# main.net
KiCad netlist of a schematic drawn in Altium Designer
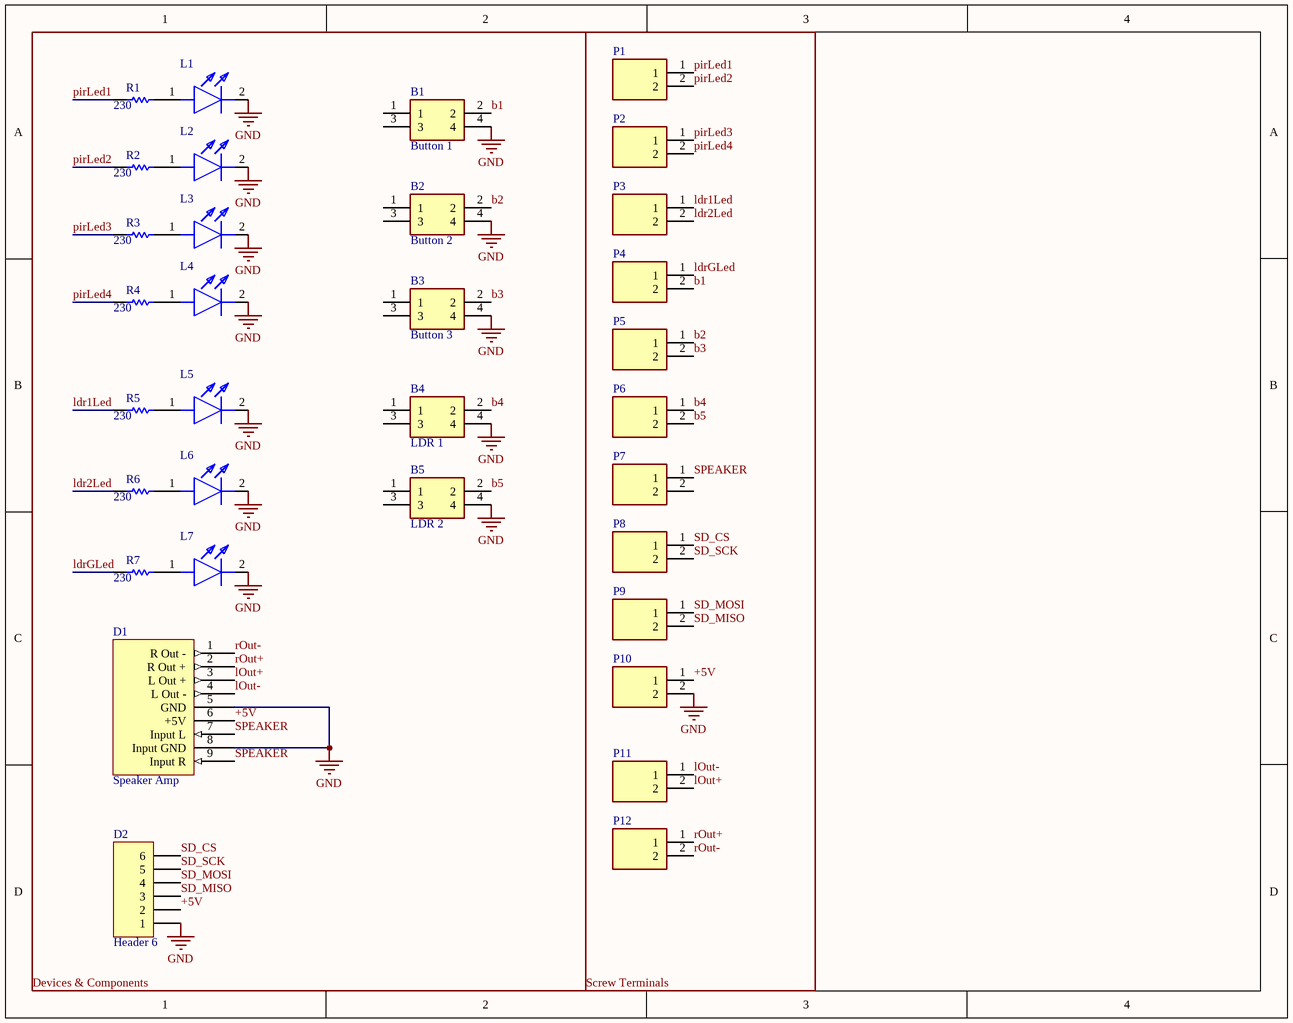
[diagram p0: main.SchDoc]

(export (version "E")
  (design (tool "Eeschema 10.0.6"))
  (components
    (comp (ref "B1")
      (value "Button 1")
      (footprint "SamacSys:FSM4JH")
      (description "Tactile Pushbutton")
      (fields
        (field (name "MANUFACTURER_PART_NUMBER") "FSM2JAH")
        (field (name "MOUSER PART NUMBER") "506-FSM2JAH")
      )
      (libsource (lib "*") (part "FSM2JAH"))
    )
    (comp (ref "B2")
      (value "Button 2")
      (footprint "SamacSys:FSM4JH")
      (description "Tactile Pushbutton")
      (fields
        (field (name "MANUFACTURER_PART_NUMBER") "FSM2JAH")
        (field (name "MOUSER PART NUMBER") "506-FSM2JAH")
      )
      (libsource (lib "*") (part "FSM2JAH"))
    )
    (comp (ref "B3")
      (value "Button 3")
      (footprint "SamacSys:FSM4JH")
      (description "Tactile Pushbutton")
      (fields
        (field (name "MANUFACTURER_PART_NUMBER") "FSM2JAH")
        (field (name "MOUSER PART NUMBER") "506-FSM2JAH")
      )
      (libsource (lib "*") (part "FSM2JAH"))
    )
    (comp (ref "B4")
      (value "LDR 1")
      (footprint "SamacSys:FSM4JH")
      (description "Tactile Pushbutton")
      (fields
        (field (name "MANUFACTURER_PART_NUMBER") "FSM2JAH")
        (field (name "MOUSER PART NUMBER") "506-FSM2JAH")
      )
      (libsource (lib "*") (part "FSM2JAH"))
    )
    (comp (ref "B5")
      (value "LDR 2")
      (footprint "SamacSys:FSM4JH")
      (description "Tactile Pushbutton")
      (fields
        (field (name "MANUFACTURER_PART_NUMBER") "FSM2JAH")
        (field (name "MOUSER PART NUMBER") "506-FSM2JAH")
      )
      (libsource (lib "*") (part "FSM2JAH"))
    )
    (comp (ref "D1")
      (value "Speaker Amp")
      (footprint "HiLetgo PAM8403 Amp Module")
      (description "https://www.amazon.com/dp/B01DKAI51M?psc=1&smid=A30QSGOJR8LMXA&ref_=chk_typ_imgToDp")
      (libsource (lib "speaker_amp") (part "HiLetgo PAM8403 Module"))
    )
    (comp (ref "D2")
      (value "Header 6")
      (footprint "HDR1X6")
      (description "Header, 6-Pin")
      (fields (field (name "PUBLISHER") "Altium Limited"))
      (libsource (lib "Miscellaneous Connectors") (part "Header 6"))
    )
    (comp (ref "L1")
      (value "~")
      (footprint "SamacSys:C5SMFRJECT0W0BB2")
      (description "LED")
      (fields
        (field (name "MANUFACTURER_PART_NUMBER") "C5SMF-RJE-CT0W0BB2")
        (field (name "MOUSER PART NUMBER") "941-C5SMFRJECT0W0BB2")
      )
      (libsource (lib "*") (part "C5SMF-RJE-CT0W0BB2"))
    )
    (comp (ref "L2")
      (value "~")
      (footprint "SamacSys:C5SMFRJECT0W0BB2")
      (description "LED")
      (fields
        (field (name "MANUFACTURER_PART_NUMBER") "C5SMF-RJE-CT0W0BB2")
        (field (name "MOUSER PART NUMBER") "941-C5SMFRJECT0W0BB2")
      )
      (libsource (lib "*") (part "C5SMF-RJE-CT0W0BB2"))
    )
    (comp (ref "L3")
      (value "~")
      (footprint "SamacSys:C5SMFRJECT0W0BB2")
      (description "LED")
      (fields
        (field (name "MANUFACTURER_PART_NUMBER") "C5SMF-RJE-CT0W0BB2")
        (field (name "MOUSER PART NUMBER") "941-C5SMFRJECT0W0BB2")
      )
      (libsource (lib "*") (part "C5SMF-RJE-CT0W0BB2"))
    )
    (comp (ref "L4")
      (value "~")
      (footprint "SamacSys:C5SMFRJECT0W0BB2")
      (description "LED")
      (fields
        (field (name "MANUFACTURER_PART_NUMBER") "C5SMF-RJE-CT0W0BB2")
        (field (name "MOUSER PART NUMBER") "941-C5SMFRJECT0W0BB2")
      )
      (libsource (lib "*") (part "C5SMF-RJE-CT0W0BB2"))
    )
    (comp (ref "L5")
      (value "~")
      (footprint "SamacSys:C5SMFRJECT0W0BB2")
      (description "LED")
      (fields
        (field (name "MANUFACTURER_PART_NUMBER") "C5SMF-RJE-CT0W0BB2")
        (field (name "MOUSER PART NUMBER") "941-C5SMFRJECT0W0BB2")
      )
      (libsource (lib "*") (part "C5SMF-RJE-CT0W0BB2"))
    )
    (comp (ref "L6")
      (value "~")
      (footprint "SamacSys:C5SMFRJECT0W0BB2")
      (description "LED")
      (fields
        (field (name "MANUFACTURER_PART_NUMBER") "C5SMF-RJE-CT0W0BB2")
        (field (name "MOUSER PART NUMBER") "941-C5SMFRJECT0W0BB2")
      )
      (libsource (lib "*") (part "C5SMF-RJE-CT0W0BB2"))
    )
    (comp (ref "L7")
      (value "~")
      (footprint "SamacSys:C5SMFRJECT0W0BB2")
      (description "LED")
      (fields
        (field (name "MANUFACTURER_PART_NUMBER") "C5SMF-RJE-CT0W0BB2")
        (field (name "MOUSER PART NUMBER") "941-C5SMFRJECT0W0BB2")
      )
      (libsource (lib "*") (part "C5SMF-RJE-CT0W0BB2"))
    )
    (comp (ref "P1")
      (value "~")
      (footprint "SamacSys:TB00250002BE")
      (description "Connector")
      (fields
        (field (name "MANUFACTURER_PART_NUMBER") "TB002-500-02BE")
        (field (name "MOUSER PART NUMBER") "490-TB002-500-02BE")
      )
      (libsource (lib "*") (part "TB002-500-02BE"))
    )
    (comp (ref "P2")
      (value "~")
      (footprint "SamacSys:TB00250002BE")
      (description "Connector")
      (fields
        (field (name "MANUFACTURER_PART_NUMBER") "TB002-500-02BE")
        (field (name "MOUSER PART NUMBER") "490-TB002-500-02BE")
      )
      (libsource (lib "*") (part "TB002-500-02BE"))
    )
    (comp (ref "P3")
      (value "~")
      (footprint "SamacSys:TB00250002BE")
      (description "Connector")
      (fields
        (field (name "MANUFACTURER_PART_NUMBER") "TB002-500-02BE")
        (field (name "MOUSER PART NUMBER") "490-TB002-500-02BE")
      )
      (libsource (lib "*") (part "TB002-500-02BE"))
    )
    (comp (ref "P4")
      (value "~")
      (footprint "SamacSys:TB00250002BE")
      (description "Connector")
      (fields
        (field (name "MANUFACTURER_PART_NUMBER") "TB002-500-02BE")
        (field (name "MOUSER PART NUMBER") "490-TB002-500-02BE")
      )
      (libsource (lib "*") (part "TB002-500-02BE"))
    )
    (comp (ref "P5")
      (value "~")
      (footprint "SamacSys:TB00250002BE")
      (description "Connector")
      (fields
        (field (name "MANUFACTURER_PART_NUMBER") "TB002-500-02BE")
        (field (name "MOUSER PART NUMBER") "490-TB002-500-02BE")
      )
      (libsource (lib "*") (part "TB002-500-02BE"))
    )
    (comp (ref "P6")
      (value "~")
      (footprint "SamacSys:TB00250002BE")
      (description "Connector")
      (fields
        (field (name "MANUFACTURER_PART_NUMBER") "TB002-500-02BE")
        (field (name "MOUSER PART NUMBER") "490-TB002-500-02BE")
      )
      (libsource (lib "*") (part "TB002-500-02BE"))
    )
    (comp (ref "P7")
      (value "~")
      (footprint "SamacSys:TB00250002BE")
      (description "Connector")
      (fields
        (field (name "MANUFACTURER_PART_NUMBER") "TB002-500-02BE")
        (field (name "MOUSER PART NUMBER") "490-TB002-500-02BE")
      )
      (libsource (lib "*") (part "TB002-500-02BE"))
    )
    (comp (ref "P8")
      (value "~")
      (footprint "SamacSys:TB00250002BE")
      (description "Connector")
      (fields
        (field (name "MANUFACTURER_PART_NUMBER") "TB002-500-02BE")
        (field (name "MOUSER PART NUMBER") "490-TB002-500-02BE")
      )
      (libsource (lib "*") (part "TB002-500-02BE"))
    )
    (comp (ref "P9")
      (value "~")
      (footprint "SamacSys:TB00250002BE")
      (description "Connector")
      (fields
        (field (name "MANUFACTURER_PART_NUMBER") "TB002-500-02BE")
        (field (name "MOUSER PART NUMBER") "490-TB002-500-02BE")
      )
      (libsource (lib "*") (part "TB002-500-02BE"))
    )
    (comp (ref "P10")
      (value "~")
      (footprint "SamacSys:TB00250002BE")
      (description "Connector")
      (fields
        (field (name "MANUFACTURER_PART_NUMBER") "TB002-500-02BE")
        (field (name "MOUSER PART NUMBER") "490-TB002-500-02BE")
      )
      (libsource (lib "*") (part "TB002-500-02BE"))
    )
    (comp (ref "P11")
      (value "~")
      (footprint "SamacSys:TB00250002BE")
      (description "Connector")
      (fields
        (field (name "MANUFACTURER_PART_NUMBER") "TB002-500-02BE")
        (field (name "MOUSER PART NUMBER") "490-TB002-500-02BE")
      )
      (libsource (lib "*") (part "TB002-500-02BE"))
    )
    (comp (ref "P12")
      (value "~")
      (footprint "SamacSys:TB00250002BE")
      (description "Connector")
      (fields
        (field (name "MANUFACTURER_PART_NUMBER") "TB002-500-02BE")
        (field (name "MOUSER PART NUMBER") "490-TB002-500-02BE")
      )
      (libsource (lib "*") (part "TB002-500-02BE"))
    )
    (comp (ref "R1")
      (value "230")
      (footprint "AXIAL-0.3")
      (description "Resistor")
      (fields (field (name "Comment") "230 Ohm") (field (name "PUBLISHER") "Altium Limited"))
      (libsource (lib "Miscellaneous Devices") (part "Res1"))
    )
    (comp (ref "R2")
      (value "230")
      (footprint "AXIAL-0.3")
      (description "Resistor")
      (fields (field (name "Comment") "230 Ohm") (field (name "PUBLISHER") "Altium Limited"))
      (libsource (lib "Miscellaneous Devices") (part "Res1"))
    )
    (comp (ref "R3")
      (value "230")
      (footprint "AXIAL-0.3")
      (description "Resistor")
      (fields (field (name "Comment") "230 Ohm") (field (name "PUBLISHER") "Altium Limited"))
      (libsource (lib "Miscellaneous Devices") (part "Res1"))
    )
    (comp (ref "R4")
      (value "230")
      (footprint "AXIAL-0.3")
      (description "Resistor")
      (fields (field (name "Comment") "230 Ohm") (field (name "PUBLISHER") "Altium Limited"))
      (libsource (lib "Miscellaneous Devices") (part "Res1"))
    )
    (comp (ref "R5")
      (value "230")
      (footprint "AXIAL-0.3")
      (description "Resistor")
      (fields (field (name "Comment") "230 Ohm") (field (name "PUBLISHER") "Altium Limited"))
      (libsource (lib "Miscellaneous Devices") (part "Res1"))
    )
    (comp (ref "R6")
      (value "230")
      (footprint "AXIAL-0.3")
      (description "Resistor")
      (fields (field (name "Comment") "230 Ohm") (field (name "PUBLISHER") "Altium Limited"))
      (libsource (lib "Miscellaneous Devices") (part "Res1"))
    )
    (comp (ref "R7")
      (value "230")
      (footprint "AXIAL-0.3")
      (description "Resistor")
      (fields (field (name "Comment") "230 Ohm") (field (name "PUBLISHER") "Altium Limited"))
      (libsource (lib "Miscellaneous Devices") (part "Res1"))
    )
  )
  (nets
    (net (code "1") (name "/+5V") (class "Default")
      (node (ref "D1") (pin "6") (pinfunction "+5V_6") (pintype "power_in"))
      (node (ref "D2") (pin "2") (pinfunction "2_2") (pintype "passive"))
      (node (ref "P10") (pin "1") (pinfunction "1_1") (pintype "passive"))
    )
    (net (code "2") (name "/SD_CS") (class "Default")
      (node (ref "D2") (pin "6") (pinfunction "6_6") (pintype "passive"))
      (node (ref "P8") (pin "1") (pinfunction "1_1") (pintype "passive"))
    )
    (net (code "3") (name "/SD_MISO") (class "Default")
      (node (ref "D2") (pin "3") (pinfunction "3_3") (pintype "passive"))
      (node (ref "P9") (pin "2") (pinfunction "2_2") (pintype "passive"))
    )
    (net (code "4") (name "/SD_MOSI") (class "Default")
      (node (ref "D2") (pin "4") (pinfunction "4_4") (pintype "passive"))
      (node (ref "P9") (pin "1") (pinfunction "1_1") (pintype "passive"))
    )
    (net (code "5") (name "/SD_SCK") (class "Default")
      (node (ref "D2") (pin "5") (pinfunction "5_5") (pintype "passive"))
      (node (ref "P8") (pin "2") (pinfunction "2_2") (pintype "passive"))
    )
    (net (code "6") (name "/SPEAKER") (class "Default")
      (node (ref "D1") (pin "7") (pinfunction "Input_L_7") (pintype "input"))
      (node (ref "D1") (pin "9") (pinfunction "Input_R_9") (pintype "input"))
      (node (ref "P7") (pin "1") (pinfunction "1_1") (pintype "passive"))
    )
    (net (code "7") (name "/b1") (class "Default")
      (node (ref "B1") (pin "2") (pinfunction "2_2") (pintype "passive"))
      (node (ref "P4") (pin "2") (pinfunction "2_2") (pintype "passive"))
    )
    (net (code "8") (name "/b2") (class "Default")
      (node (ref "B2") (pin "2") (pinfunction "2_2") (pintype "passive"))
      (node (ref "P5") (pin "1") (pinfunction "1_1") (pintype "passive"))
    )
    (net (code "9") (name "/b3") (class "Default")
      (node (ref "B3") (pin "2") (pinfunction "2_2") (pintype "passive"))
      (node (ref "P5") (pin "2") (pinfunction "2_2") (pintype "passive"))
    )
    (net (code "10") (name "/b4") (class "Default")
      (node (ref "B4") (pin "2") (pinfunction "2_2") (pintype "passive"))
      (node (ref "P6") (pin "1") (pinfunction "1_1") (pintype "passive"))
    )
    (net (code "11") (name "/b5") (class "Default")
      (node (ref "B5") (pin "2") (pinfunction "2_2") (pintype "passive"))
      (node (ref "P6") (pin "2") (pinfunction "2_2") (pintype "passive"))
    )
    (net (code "12") (name "/lOut+") (class "Default")
      (node (ref "D1") (pin "3") (pinfunction "L_Out_+_3") (pintype "output"))
      (node (ref "P11") (pin "2") (pinfunction "2_2") (pintype "passive"))
    )
    (net (code "13") (name "/lOut-") (class "Default")
      (node (ref "D1") (pin "4") (pinfunction "L_Out_-_4") (pintype "output"))
      (node (ref "P11") (pin "1") (pinfunction "1_1") (pintype "passive"))
    )
    (net (code "14") (name "/ldr1Led") (class "Default")
      (node (ref "P3") (pin "1") (pinfunction "1_1") (pintype "passive"))
      (node (ref "R5") (pin "1") (pinfunction "1_1") (pintype "passive"))
    )
    (net (code "15") (name "/ldr2Led") (class "Default")
      (node (ref "P3") (pin "2") (pinfunction "2_2") (pintype "passive"))
      (node (ref "R6") (pin "1") (pinfunction "1_1") (pintype "passive"))
    )
    (net (code "16") (name "/ldrGLed") (class "Default")
      (node (ref "P4") (pin "1") (pinfunction "1_1") (pintype "passive"))
      (node (ref "R7") (pin "1") (pinfunction "1_1") (pintype "passive"))
    )
    (net (code "17") (name "/pirLed1") (class "Default")
      (node (ref "P1") (pin "1") (pinfunction "1_1") (pintype "passive"))
      (node (ref "R1") (pin "1") (pinfunction "1_1") (pintype "passive"))
    )
    (net (code "18") (name "/pirLed2") (class "Default")
      (node (ref "P1") (pin "2") (pinfunction "2_2") (pintype "passive"))
      (node (ref "R2") (pin "1") (pinfunction "1_1") (pintype "passive"))
    )
    (net (code "19") (name "/pirLed3") (class "Default")
      (node (ref "P2") (pin "1") (pinfunction "1_1") (pintype "passive"))
      (node (ref "R3") (pin "1") (pinfunction "1_1") (pintype "passive"))
    )
    (net (code "20") (name "/pirLed4") (class "Default")
      (node (ref "P2") (pin "2") (pinfunction "2_2") (pintype "passive"))
      (node (ref "R4") (pin "1") (pinfunction "1_1") (pintype "passive"))
    )
    (net (code "21") (name "/rOut+") (class "Default")
      (node (ref "D1") (pin "2") (pinfunction "R_Out_+_2") (pintype "output"))
      (node (ref "P12") (pin "1") (pinfunction "1_1") (pintype "passive"))
    )
    (net (code "22") (name "/rOut-") (class "Default")
      (node (ref "D1") (pin "1") (pinfunction "R_Out_-_1") (pintype "output"))
      (node (ref "P12") (pin "2") (pinfunction "2_2") (pintype "passive"))
    )
    (net (code "23") (name "GND") (class "Default")
      (node (ref "B1") (pin "4") (pinfunction "4_4") (pintype "passive"))
      (node (ref "B2") (pin "4") (pinfunction "4_4") (pintype "passive"))
      (node (ref "B3") (pin "4") (pinfunction "4_4") (pintype "passive"))
      (node (ref "B4") (pin "4") (pinfunction "4_4") (pintype "passive"))
      (node (ref "B5") (pin "4") (pinfunction "4_4") (pintype "passive"))
      (node (ref "D1") (pin "5") (pinfunction "GND_5") (pintype "power_in"))
      (node (ref "D1") (pin "8") (pinfunction "Input_GND_8") (pintype "power_in"))
      (node (ref "D2") (pin "1") (pinfunction "1_1") (pintype "passive"))
      (node (ref "L1") (pin "2") (pinfunction "K_2") (pintype "passive"))
      (node (ref "L2") (pin "2") (pinfunction "K_2") (pintype "passive"))
      (node (ref "L3") (pin "2") (pinfunction "K_2") (pintype "passive"))
      (node (ref "L4") (pin "2") (pinfunction "K_2") (pintype "passive"))
      (node (ref "L5") (pin "2") (pinfunction "K_2") (pintype "passive"))
      (node (ref "L6") (pin "2") (pinfunction "K_2") (pintype "passive"))
      (node (ref "L7") (pin "2") (pinfunction "K_2") (pintype "passive"))
      (node (ref "P10") (pin "2") (pinfunction "2_2") (pintype "passive"))
    )
    (net (code "24") (name "Net-(L1-A)") (class "Default")
      (node (ref "L1") (pin "1") (pinfunction "A_1") (pintype "passive"))
      (node (ref "R1") (pin "2") (pinfunction "2_2") (pintype "passive"))
    )
    (net (code "25") (name "Net-(L2-A)") (class "Default")
      (node (ref "L2") (pin "1") (pinfunction "A_1") (pintype "passive"))
      (node (ref "R2") (pin "2") (pinfunction "2_2") (pintype "passive"))
    )
    (net (code "26") (name "Net-(L3-A)") (class "Default")
      (node (ref "L3") (pin "1") (pinfunction "A_1") (pintype "passive"))
      (node (ref "R3") (pin "2") (pinfunction "2_2") (pintype "passive"))
    )
    (net (code "27") (name "Net-(L4-A)") (class "Default")
      (node (ref "L4") (pin "1") (pinfunction "A_1") (pintype "passive"))
      (node (ref "R4") (pin "2") (pinfunction "2_2") (pintype "passive"))
    )
    (net (code "28") (name "Net-(L5-A)") (class "Default")
      (node (ref "L5") (pin "1") (pinfunction "A_1") (pintype "passive"))
      (node (ref "R5") (pin "2") (pinfunction "2_2") (pintype "passive"))
    )
    (net (code "29") (name "Net-(L6-A)") (class "Default")
      (node (ref "L6") (pin "1") (pinfunction "A_1") (pintype "passive"))
      (node (ref "R6") (pin "2") (pinfunction "2_2") (pintype "passive"))
    )
    (net (code "30") (name "Net-(L7-A)") (class "Default")
      (node (ref "L7") (pin "1") (pinfunction "A_1") (pintype "passive"))
      (node (ref "R7") (pin "2") (pinfunction "2_2") (pintype "passive"))
    )
    (net (code "31") (name "unconnected-(B1-Pad1)") (class "Default")
      (node (ref "B1") (pin "1") (pinfunction "1_1") (pintype "passive"))
    )
    (net (code "32") (name "unconnected-(B1-Pad3)") (class "Default")
      (node (ref "B1") (pin "3") (pinfunction "3_3") (pintype "passive"))
    )
    (net (code "33") (name "unconnected-(B2-Pad1)") (class "Default")
      (node (ref "B2") (pin "1") (pinfunction "1_1") (pintype "passive"))
    )
    (net (code "34") (name "unconnected-(B2-Pad3)") (class "Default")
      (node (ref "B2") (pin "3") (pinfunction "3_3") (pintype "passive"))
    )
    (net (code "35") (name "unconnected-(B3-Pad1)") (class "Default")
      (node (ref "B3") (pin "1") (pinfunction "1_1") (pintype "passive"))
    )
    (net (code "36") (name "unconnected-(B3-Pad3)") (class "Default")
      (node (ref "B3") (pin "3") (pinfunction "3_3") (pintype "passive"))
    )
    (net (code "37") (name "unconnected-(B4-Pad1)") (class "Default")
      (node (ref "B4") (pin "1") (pinfunction "1_1") (pintype "passive"))
    )
    (net (code "38") (name "unconnected-(B4-Pad3)") (class "Default")
      (node (ref "B4") (pin "3") (pinfunction "3_3") (pintype "passive"))
    )
    (net (code "39") (name "unconnected-(B5-Pad1)") (class "Default")
      (node (ref "B5") (pin "1") (pinfunction "1_1") (pintype "passive"))
    )
    (net (code "40") (name "unconnected-(B5-Pad3)") (class "Default")
      (node (ref "B5") (pin "3") (pinfunction "3_3") (pintype "passive"))
    )
    (net (code "41") (name "unconnected-(P7-Pad2)") (class "Default")
      (node (ref "P7") (pin "2") (pinfunction "2_2") (pintype "passive"))
    )
  )
)
